# ultrasonic_distance_meter.net
KiCad netlist of a schematic drawn in EAGLE
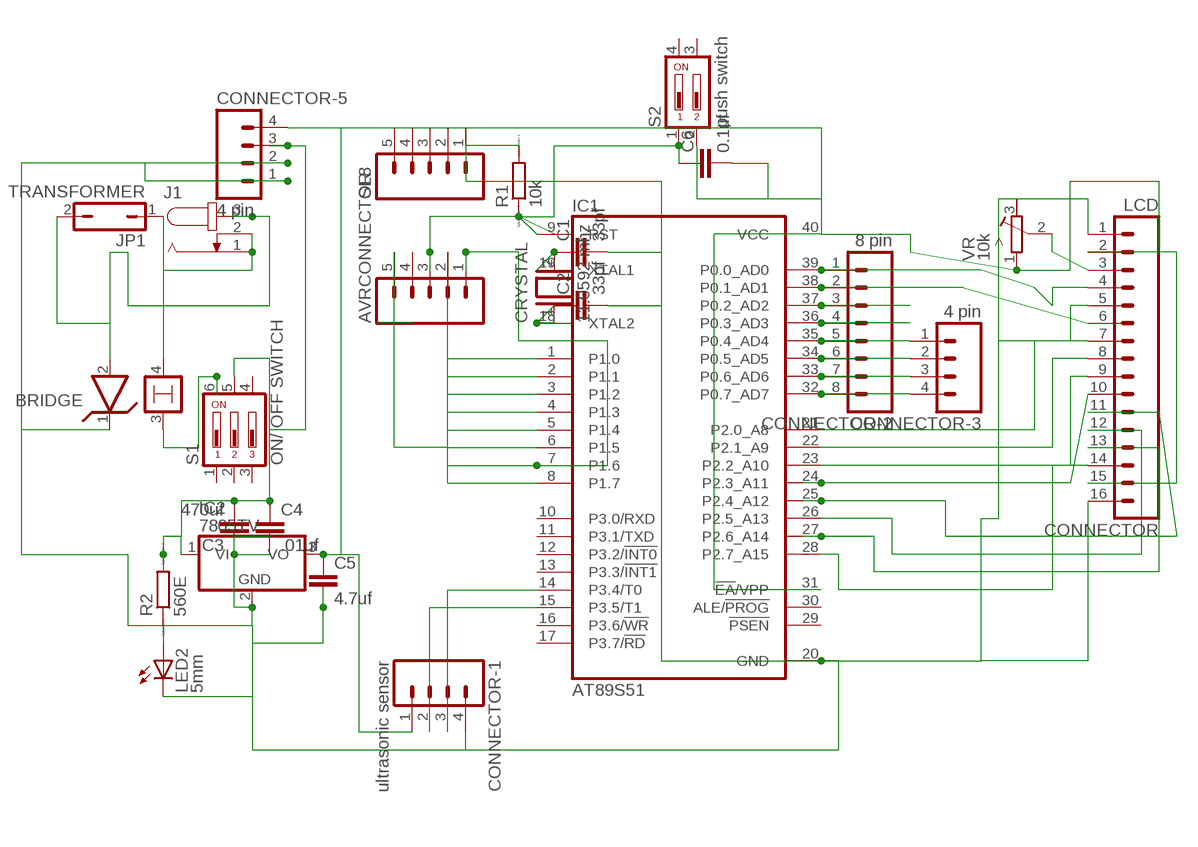
[diagram p0: schematic, sheet 1]

(export (version "E")
  (design (tool "Eeschema 10.0.6"))
  (components
    (comp (ref "AVRCONNECTOR")
      (value "M05")
      (footprint "eagle-import:05P")
      (libsource (lib "eagle-import") (part "M05"))
    )
    (comp (ref "BRIDGE")
      (value "LM399H")
      (footprint "eagle-import:TO39_4")
      (libsource (lib "eagle-import") (part "LM399H"))
    )
    (comp (ref "C1")
      (value "33pf")
      (footprint "eagle-import:C025-024X044")
      (libsource (lib "eagle-import") (part "C-EU025-024X044"))
    )
    (comp (ref "C2")
      (value "33pf")
      (footprint "eagle-import:C025-024X044")
      (libsource (lib "eagle-import") (part "C-EU025-024X044"))
    )
    (comp (ref "C3")
      (value "470uf")
      (footprint "eagle-import:C5B7.2")
      (libsource (lib "eagle-import") (part "C5/7.2"))
    )
    (comp (ref "C4")
      (value ".01uf")
      (footprint "eagle-import:C2.5-3")
      (libsource (lib "eagle-import") (part "C2,5-3"))
    )
    (comp (ref "C5")
      (value "4.7uf")
      (footprint "eagle-import:C2.5-3")
      (libsource (lib "eagle-import") (part "C2,5-3"))
    )
    (comp (ref "C6")
      (value "0.1uf")
      (footprint "eagle-import:C2.5-6")
      (libsource (lib "eagle-import") (part "C2.5/6"))
    )
    (comp (ref "CONNECTOR")
      (value "LCD")
      (footprint "eagle-import:16P")
      (libsource (lib "eagle-import") (part "M16"))
    )
    (comp (ref "CONNECTOR-1")
      (value "ultrasonic sensor")
      (footprint "eagle-import:04P")
      (fields (field (name "OC_FARNELL") "unknown") (field (name "OC_NEWARK") "unknown"))
      (libsource (lib "eagle-import") (part "M04"))
    )
    (comp (ref "CONNECTOR-2")
      (value "8 pin")
      (footprint "eagle-import:08P")
      (libsource (lib "eagle-import") (part "M08"))
    )
    (comp (ref "CONNECTOR-3")
      (value "4 pin")
      (footprint "eagle-import:04P")
      (fields (field (name "OC_FARNELL") "unknown") (field (name "OC_NEWARK") "unknown"))
      (libsource (lib "eagle-import") (part "M04"))
    )
    (comp (ref "CONNECTOR-5")
      (value "4 pin")
      (footprint "eagle-import:04P")
      (libsource (lib "eagle-import") (part "M04"))
    )
    (comp (ref "CRYSTAL")
      (value "11.0592 mhz")
      (footprint "eagle-import:QS")
      (libsource (lib "eagle-import") (part "XTAL/S"))
    )
    (comp (ref "IC1")
      (value "AT89S51")
      (footprint "eagle-import:DIL40")
      (libsource (lib "eagle-import") (part "AT89C51-PC12"))
    )
    (comp (ref "IC2")
      (value "7805TV")
      (footprint "eagle-import:TO220V")
      (libsource (lib "eagle-import") (part "78TV05"))
    )
    (comp (ref "J1")
      (value "JACK-PLUG0")
      (footprint "eagle-import:SPC4077")
      (libsource (lib "eagle-import") (part "JACK-PLUG0"))
    )
    (comp (ref "JP1")
      (value "TRANSFORMER")
      (footprint "eagle-import:JP1")
      (libsource (lib "eagle-import") (part "JP1Q"))
    )
    (comp (ref "LED2")
      (value "5mm")
      (footprint "eagle-import:LED5MM")
      (libsource (lib "eagle-import") (part "LED5MM"))
    )
    (comp (ref "R1")
      (value "10k")
      (footprint "eagle-import:0204_7")
      (libsource (lib "eagle-import") (part "R0204/7"))
    )
    (comp (ref "R2")
      (value "560E")
      (footprint "eagle-import:0204_7")
      (libsource (lib "eagle-import") (part "R0204/7"))
    )
    (comp (ref "S1")
      (value "ON/ OFF SWITCH")
      (footprint "eagle-import:DA-03")
      (fields (field (name "MPN") "MCDA03"))
      (libsource (lib "eagle-import") (part "DA03"))
    )
    (comp (ref "S2")
      (value "push switch")
      (footprint "eagle-import:DP-02")
      (fields (field (name "MPN") "MCDP02"))
      (libsource (lib "eagle-import") (part "DP02"))
    )
    (comp (ref "SL8")
      (value "M05")
      (footprint "eagle-import:05P")
      (libsource (lib "eagle-import") (part "M05"))
    )
    (comp (ref "VR")
      (value "10k")
      (footprint "eagle-import:RTRIM64P")
      (libsource (lib "eagle-import") (part "R-TRIMM64P"))
    )
  )
  (nets
    (net (code "1") (name "/N$39") (class "Default")
      (node (ref "C5") (pin "1") (pinfunction "1_1") (pintype "passive"))
      (node (ref "C6") (pin "2") (pinfunction "2_2") (pintype "passive"))
      (node (ref "CONNECTOR") (pin "15") (pinfunction "15_15") (pintype "passive"))
      (node (ref "CONNECTOR") (pin "2") (pinfunction "2_2") (pintype "passive"))
      (node (ref "CONNECTOR-1") (pin "1") (pinfunction "1_1") (pintype "passive"))
      (node (ref "CONNECTOR-5") (pin "4") (pinfunction "4_4") (pintype "passive"))
      (node (ref "IC1") (pin "31") (pinfunction "~{EA}/VPP_31") (pintype "input"))
      (node (ref "IC1") (pin "40") (pinfunction "VCC_40") (pintype "power_in"))
      (node (ref "IC2") (pin "3") (pinfunction "VO_3") (pintype "passive"))
      (node (ref "S2") (pin "2") (pinfunction "2_2") (pintype "passive"))
      (node (ref "VR") (pin "1") (pinfunction "E_1") (pintype "passive"))
    )
    (net (code "2") (name "Net-(BRIDGE-Pad2)") (class "Default")
      (node (ref "BRIDGE") (pin "2") (pinfunction "2_2") (pintype "input"))
      (node (ref "J1") (pin "3") (pinfunction "3_3") (pintype "passive"))
      (node (ref "JP1") (pin "2") (pinfunction "2_2") (pintype "passive"))
    )
    (net (code "3") (name "Net-(BRIDGE-Pad3)") (class "Default")
      (node (ref "BRIDGE") (pin "3") (pinfunction "3_3") (pintype "input"))
      (node (ref "S1") (pin "6") (pinfunction "6_6") (pintype "passive"))
    )
    (net (code "4") (name "Net-(BRIDGE-Pad4)") (class "Default")
      (node (ref "BRIDGE") (pin "4") (pinfunction "4_4") (pintype "input"))
      (node (ref "J1") (pin "1") (pinfunction "1_1") (pintype "passive"))
      (node (ref "J1") (pin "2") (pinfunction "2_2") (pintype "passive"))
      (node (ref "JP1") (pin "1") (pinfunction "1_1") (pintype "passive"))
    )
    (net (code "5") (name "Net-(IC1-GND)") (class "Default")
      (node (ref "BRIDGE") (pin "1") (pinfunction "1_1") (pintype "input"))
      (node (ref "C1") (pin "2") (pinfunction "2_2") (pintype "passive"))
      (node (ref "C2") (pin "2") (pinfunction "2_2") (pintype "passive"))
      (node (ref "C3") (pin "1") (pinfunction "1_1") (pintype "passive"))
      (node (ref "C4") (pin "2") (pinfunction "2_2") (pintype "passive"))
      (node (ref "C5") (pin "2") (pinfunction "2_2") (pintype "passive"))
      (node (ref "CONNECTOR") (pin "1") (pinfunction "1_1") (pintype "passive"))
      (node (ref "CONNECTOR") (pin "16") (pinfunction "16_16") (pintype "passive"))
      (node (ref "CONNECTOR") (pin "5") (pinfunction "5_5") (pintype "passive"))
      (node (ref "CONNECTOR-1") (pin "4") (pinfunction "4_4") (pintype "passive"))
      (node (ref "CONNECTOR-5") (pin "1") (pinfunction "1_1") (pintype "passive"))
      (node (ref "CONNECTOR-5") (pin "2") (pinfunction "2_2") (pintype "passive"))
      (node (ref "IC1") (pin "20") (pinfunction "GND_20") (pintype "power_in"))
      (node (ref "IC2") (pin "2") (pinfunction "GND_2") (pintype "passive"))
      (node (ref "LED2") (pin "K") (pinfunction "C_K") (pintype "passive"))
      (node (ref "R1") (pin "2") (pinfunction "2_2") (pintype "passive"))
      (node (ref "SL8") (pin "1") (pinfunction "1_1") (pintype "passive"))
      (node (ref "VR") (pin "3") (pinfunction "A_3") (pintype "passive"))
    )
    (net (code "6") (name "Net-(IC1-P0.0_AD0)") (class "Default")
      (node (ref "CONNECTOR") (pin "4") (pinfunction "4_4") (pintype "passive"))
      (node (ref "CONNECTOR-2") (pin "1") (pinfunction "1_1") (pintype "passive"))
      (node (ref "IC1") (pin "39") (pinfunction "P0.0_AD0_39") (pintype "bidirectional"))
    )
    (net (code "7") (name "Net-(IC1-P0.1_AD1)") (class "Default")
      (node (ref "CONNECTOR") (pin "6") (pinfunction "6_6") (pintype "passive"))
      (node (ref "CONNECTOR-2") (pin "2") (pinfunction "2_2") (pintype "passive"))
      (node (ref "IC1") (pin "38") (pinfunction "P0.1_AD1_38") (pintype "bidirectional"))
    )
    (net (code "8") (name "Net-(IC1-P0.2_AD2)") (class "Default")
      (node (ref "CONNECTOR-2") (pin "3") (pinfunction "3_3") (pintype "passive"))
      (node (ref "IC1") (pin "37") (pinfunction "P0.2_AD2_37") (pintype "bidirectional"))
    )
    (net (code "9") (name "Net-(IC1-P0.3_AD3)") (class "Default")
      (node (ref "CONNECTOR-2") (pin "4") (pinfunction "4_4") (pintype "passive"))
      (node (ref "IC1") (pin "36") (pinfunction "P0.3_AD3_36") (pintype "bidirectional"))
    )
    (net (code "10") (name "Net-(IC1-P0.4_AD4)") (class "Default")
      (node (ref "CONNECTOR-2") (pin "5") (pinfunction "5_5") (pintype "passive"))
      (node (ref "CONNECTOR-3") (pin "1") (pinfunction "1_1") (pintype "passive"))
      (node (ref "IC1") (pin "35") (pinfunction "P0.4_AD4_35") (pintype "bidirectional"))
    )
    (net (code "11") (name "Net-(IC1-P0.5_AD5)") (class "Default")
      (node (ref "CONNECTOR-2") (pin "6") (pinfunction "6_6") (pintype "passive"))
      (node (ref "CONNECTOR-3") (pin "2") (pinfunction "2_2") (pintype "passive"))
      (node (ref "IC1") (pin "34") (pinfunction "P0.5_AD5_34") (pintype "bidirectional"))
    )
    (net (code "12") (name "Net-(IC1-P0.6_AD6)") (class "Default")
      (node (ref "CONNECTOR-2") (pin "7") (pinfunction "7_7") (pintype "passive"))
      (node (ref "CONNECTOR-3") (pin "3") (pinfunction "3_3") (pintype "passive"))
      (node (ref "IC1") (pin "33") (pinfunction "P0.6_AD6_33") (pintype "bidirectional"))
    )
    (net (code "13") (name "Net-(IC1-P0.7_AD7)") (class "Default")
      (node (ref "CONNECTOR-2") (pin "8") (pinfunction "8_8") (pintype "passive"))
      (node (ref "CONNECTOR-3") (pin "4") (pinfunction "4_4") (pintype "passive"))
      (node (ref "IC1") (pin "32") (pinfunction "P0.7_AD7_32") (pintype "bidirectional"))
    )
    (net (code "14") (name "Net-(IC1-P1.5)") (class "Default")
      (node (ref "AVRCONNECTOR") (pin "5") (pinfunction "5_5") (pintype "passive"))
      (node (ref "IC1") (pin "6") (pinfunction "P1.5_6") (pintype "bidirectional"))
    )
    (net (code "15") (name "Net-(IC1-P1.6)") (class "Default")
      (node (ref "AVRCONNECTOR") (pin "1") (pinfunction "1_1") (pintype "passive"))
      (node (ref "IC1") (pin "7") (pinfunction "P1.6_7") (pintype "bidirectional"))
    )
    (net (code "16") (name "Net-(IC1-P1.7)") (class "Default")
      (node (ref "AVRCONNECTOR") (pin "2") (pinfunction "2_2") (pintype "passive"))
      (node (ref "IC1") (pin "8") (pinfunction "P1.7_8") (pintype "bidirectional"))
    )
    (net (code "17") (name "Net-(IC1-P2.0_A8)") (class "Default")
      (node (ref "CONNECTOR") (pin "7") (pinfunction "7_7") (pintype "passive"))
      (node (ref "IC1") (pin "21") (pinfunction "P2.0_A8_21") (pintype "bidirectional"))
    )
    (net (code "18") (name "Net-(IC1-P2.1_A9)") (class "Default")
      (node (ref "CONNECTOR") (pin "8") (pinfunction "8_8") (pintype "passive"))
      (node (ref "IC1") (pin "22") (pinfunction "P2.1_A9_22") (pintype "bidirectional"))
    )
    (net (code "19") (name "Net-(IC1-P2.2_A10)") (class "Default")
      (node (ref "CONNECTOR") (pin "9") (pinfunction "9_9") (pintype "passive"))
      (node (ref "IC1") (pin "23") (pinfunction "P2.2_A10_23") (pintype "bidirectional"))
    )
    (net (code "20") (name "Net-(IC1-P2.3_A11)") (class "Default")
      (node (ref "CONNECTOR") (pin "10") (pinfunction "10_10") (pintype "passive"))
      (node (ref "IC1") (pin "24") (pinfunction "P2.3_A11_24") (pintype "bidirectional"))
    )
    (net (code "21") (name "Net-(IC1-P2.4_A12)") (class "Default")
      (node (ref "CONNECTOR") (pin "11") (pinfunction "11_11") (pintype "passive"))
      (node (ref "IC1") (pin "25") (pinfunction "P2.4_A12_25") (pintype "bidirectional"))
    )
    (net (code "22") (name "Net-(IC1-P2.5_A13)") (class "Default")
      (node (ref "CONNECTOR") (pin "12") (pinfunction "12_12") (pintype "passive"))
      (node (ref "IC1") (pin "26") (pinfunction "P2.5_A13_26") (pintype "bidirectional"))
    )
    (net (code "23") (name "Net-(IC1-P2.6_A14)") (class "Default")
      (node (ref "CONNECTOR") (pin "13") (pinfunction "13_13") (pintype "passive"))
      (node (ref "IC1") (pin "27") (pinfunction "P2.6_A14_27") (pintype "bidirectional"))
    )
    (net (code "24") (name "Net-(IC1-P2.7_A15)") (class "Default")
      (node (ref "CONNECTOR") (pin "14") (pinfunction "14_14") (pintype "passive"))
      (node (ref "IC1") (pin "28") (pinfunction "P2.7_A15_28") (pintype "bidirectional"))
    )
    (net (code "25") (name "Net-(IC1-P3.4{slash}T0)") (class "Default")
      (node (ref "CONNECTOR-1") (pin "3") (pinfunction "3_3") (pintype "passive"))
      (node (ref "IC1") (pin "14") (pinfunction "P3.4/T0_14") (pintype "bidirectional"))
    )
    (net (code "26") (name "Net-(IC1-P3.5{slash}T1)") (class "Default")
      (node (ref "CONNECTOR-1") (pin "2") (pinfunction "2_2") (pintype "passive"))
      (node (ref "IC1") (pin "15") (pinfunction "P3.5/T1_15") (pintype "bidirectional"))
    )
    (net (code "27") (name "Net-(IC1-RST)") (class "Default")
      (node (ref "AVRCONNECTOR") (pin "3") (pinfunction "3_3") (pintype "passive"))
      (node (ref "C6") (pin "1") (pinfunction "1_1") (pintype "passive"))
      (node (ref "IC1") (pin "9") (pinfunction "RST_9") (pintype "input"))
      (node (ref "R1") (pin "1") (pinfunction "1_1") (pintype "passive"))
      (node (ref "S2") (pin "1") (pinfunction "1_1") (pintype "passive"))
    )
    (net (code "28") (name "Net-(IC1-XTAL1)") (class "Default")
      (node (ref "C1") (pin "1") (pinfunction "1_1") (pintype "passive"))
      (node (ref "CRYSTAL") (pin "2") (pinfunction "2_2") (pintype "passive"))
      (node (ref "IC1") (pin "19") (pinfunction "XTAL1_19") (pintype "input"))
    )
    (net (code "29") (name "Net-(IC1-XTAL2)") (class "Default")
      (node (ref "C2") (pin "1") (pinfunction "1_1") (pintype "passive"))
      (node (ref "CRYSTAL") (pin "1") (pinfunction "1_1") (pintype "passive"))
      (node (ref "IC1") (pin "18") (pinfunction "XTAL2_18") (pintype "input"))
    )
    (net (code "30") (name "Net-(IC2-VI)") (class "Default")
      (node (ref "C3") (pin "2") (pinfunction "2_2") (pintype "passive"))
      (node (ref "C4") (pin "1") (pinfunction "1_1") (pintype "passive"))
      (node (ref "CONNECTOR-5") (pin "3") (pinfunction "3_3") (pintype "passive"))
      (node (ref "IC2") (pin "1") (pinfunction "VI_1") (pintype "input"))
      (node (ref "R2") (pin "2") (pinfunction "2_2") (pintype "passive"))
      (node (ref "S1") (pin "5") (pinfunction "5_5") (pintype "passive"))
    )
    (net (code "31") (name "Net-(LED2-PadA)") (class "Default")
      (node (ref "LED2") (pin "A") (pinfunction "A_A") (pintype "passive"))
      (node (ref "R2") (pin "1") (pinfunction "1_1") (pintype "passive"))
    )
    (net (code "32") (name "Net-(VR-S)") (class "Default")
      (node (ref "CONNECTOR") (pin "3") (pinfunction "3_3") (pintype "passive"))
      (node (ref "VR") (pin "2") (pinfunction "S_2") (pintype "passive"))
    )
    (net (code "33") (name "unconnected-(AVRCONNECTOR-Pad4)") (class "Default")
      (node (ref "AVRCONNECTOR") (pin "4") (pinfunction "4_4") (pintype "passive"))
    )
    (net (code "34") (name "unconnected-(IC1-ALE{slash}~{PROG}-Pad30)") (class "Default")
      (node (ref "IC1") (pin "30") (pinfunction "ALE/~{PROG}_30") (pintype "output"))
    )
    (net (code "35") (name "unconnected-(IC1-P1.0-Pad1)") (class "Default")
      (node (ref "IC1") (pin "1") (pinfunction "P1.0_1") (pintype "bidirectional"))
    )
    (net (code "36") (name "unconnected-(IC1-P1.1-Pad2)") (class "Default")
      (node (ref "IC1") (pin "2") (pinfunction "P1.1_2") (pintype "bidirectional"))
    )
    (net (code "37") (name "unconnected-(IC1-P1.2-Pad3)") (class "Default")
      (node (ref "IC1") (pin "3") (pinfunction "P1.2_3") (pintype "bidirectional"))
    )
    (net (code "38") (name "unconnected-(IC1-P1.3-Pad4)") (class "Default")
      (node (ref "IC1") (pin "4") (pinfunction "P1.3_4") (pintype "bidirectional"))
    )
    (net (code "39") (name "unconnected-(IC1-P1.4-Pad5)") (class "Default")
      (node (ref "IC1") (pin "5") (pinfunction "P1.4_5") (pintype "bidirectional"))
    )
    (net (code "40") (name "unconnected-(IC1-P3.0{slash}RXD-Pad10)") (class "Default")
      (node (ref "IC1") (pin "10") (pinfunction "P3.0/RXD_10") (pintype "bidirectional"))
    )
    (net (code "41") (name "unconnected-(IC1-P3.1{slash}TXD-Pad11)") (class "Default")
      (node (ref "IC1") (pin "11") (pinfunction "P3.1/TXD_11") (pintype "bidirectional"))
    )
    (net (code "42") (name "unconnected-(IC1-P3.2{slash}~{INT0}-Pad12)") (class "Default")
      (node (ref "IC1") (pin "12") (pinfunction "P3.2/~{INT0}_12") (pintype "bidirectional"))
    )
    (net (code "43") (name "unconnected-(IC1-P3.3{slash}~{INT1}-Pad13)") (class "Default")
      (node (ref "IC1") (pin "13") (pinfunction "P3.3/~{INT1}_13") (pintype "bidirectional"))
    )
    (net (code "44") (name "unconnected-(IC1-P3.6{slash}~{WR}-Pad16)") (class "Default")
      (node (ref "IC1") (pin "16") (pinfunction "P3.6/~{WR}_16") (pintype "bidirectional"))
    )
    (net (code "45") (name "unconnected-(IC1-P3.7{slash}~{RD}-Pad17)") (class "Default")
      (node (ref "IC1") (pin "17") (pinfunction "P3.7/~{RD}_17") (pintype "bidirectional"))
    )
    (net (code "46") (name "unconnected-(IC1-~{PSEN}-Pad29)") (class "Default")
      (node (ref "IC1") (pin "29") (pinfunction "~{PSEN}_29") (pintype "output"))
    )
    (net (code "47") (name "unconnected-(S1-Pad1)") (class "Default")
      (node (ref "S1") (pin "1") (pinfunction "1_1") (pintype "passive"))
    )
    (net (code "48") (name "unconnected-(S1-Pad2)") (class "Default")
      (node (ref "S1") (pin "2") (pinfunction "2_2") (pintype "passive"))
    )
    (net (code "49") (name "unconnected-(S1-Pad3)") (class "Default")
      (node (ref "S1") (pin "3") (pinfunction "3_3") (pintype "passive"))
    )
    (net (code "50") (name "unconnected-(S1-Pad4)") (class "Default")
      (node (ref "S1") (pin "4") (pinfunction "4_4") (pintype "passive"))
    )
    (net (code "51") (name "unconnected-(S2-Pad3)") (class "Default")
      (node (ref "S2") (pin "3") (pinfunction "3_3") (pintype "passive"))
    )
    (net (code "52") (name "unconnected-(S2-Pad4)") (class "Default")
      (node (ref "S2") (pin "4") (pinfunction "4_4") (pintype "passive"))
    )
    (net (code "53") (name "unconnected-(SL8-Pad2)") (class "Default")
      (node (ref "SL8") (pin "2") (pinfunction "2_2") (pintype "passive"))
    )
    (net (code "54") (name "unconnected-(SL8-Pad3)") (class "Default")
      (node (ref "SL8") (pin "3") (pinfunction "3_3") (pintype "passive"))
    )
    (net (code "55") (name "unconnected-(SL8-Pad4)") (class "Default")
      (node (ref "SL8") (pin "4") (pinfunction "4_4") (pintype "passive"))
    )
    (net (code "56") (name "unconnected-(SL8-Pad5)") (class "Default")
      (node (ref "SL8") (pin "5") (pinfunction "5_5") (pintype "passive"))
    )
  )
)
